# usbC_adapter.net
KiCad netlist of a schematic drawn in EAGLE
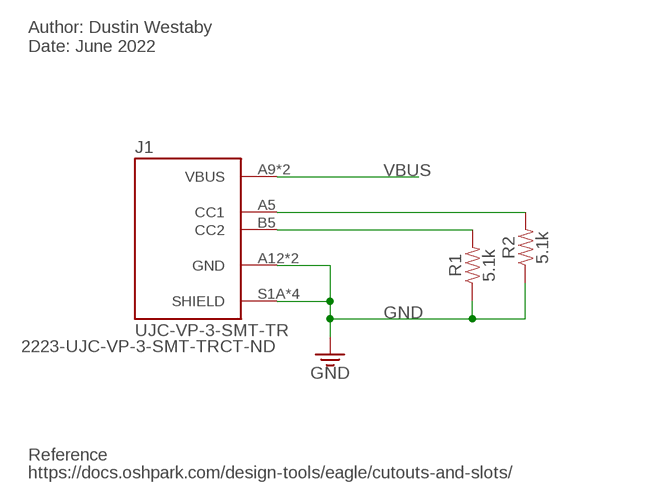
[diagram p0: schematic, sheet 1]

(export (version "E")
  (design (tool "Eeschema 10.0.6"))
  (components
    (comp (ref "J1")
      (value "UJC-VP-3-SMT-TR")
      (footprint "eagle-import:CUI_UJC-VP-3-SMT-TR")
      (fields (field (name "MANUFACTURER") "CUI Devices"))
      (libsource (lib "eagle-import") (part "UJC-VP-3-SMT-TR"))
    )
    (comp (ref "R1")
      (value "5.1k")
      (footprint "eagle-import:0402-TIGHT")
      (libsource (lib "eagle-import") (part "5.1KOHM-0402T-1/16W-1%"))
    )
    (comp (ref "R2")
      (value "5.1k")
      (footprint "eagle-import:0402-TIGHT")
      (libsource (lib "eagle-import") (part "5.1KOHM-0402T-1/16W-1%"))
    )
  )
  (nets
    (net (code "1") (name "/VBUS") (class "Default")
      (node (ref "J1") (pin "A9") (pinfunction "VBUS_A9") (pintype "power_in"))
      (node (ref "J1") (pin "B9") (pinfunction "VBUS_B9") (pintype "power_in"))
    )
    (net (code "2") (name "GND") (class "Default")
      (node (ref "J1") (pin "A12") (pinfunction "GND_A12") (pintype "power_in"))
      (node (ref "J1") (pin "B12") (pinfunction "GND_B12") (pintype "power_in"))
      (node (ref "J1") (pin "S1A") (pinfunction "SHIELD_S1A") (pintype "passive"))
      (node (ref "J1") (pin "S1B") (pinfunction "SHIELD_S1B") (pintype "passive"))
      (node (ref "J1") (pin "S2A") (pinfunction "SHIELD_S2A") (pintype "passive"))
      (node (ref "J1") (pin "S2B") (pinfunction "SHIELD_S2B") (pintype "passive"))
      (node (ref "R1") (pin "1") (pinfunction "1_1") (pintype "passive"))
      (node (ref "R2") (pin "1") (pinfunction "1_1") (pintype "passive"))
    )
    (net (code "3") (name "Net-(J1-CC1)") (class "Default")
      (node (ref "J1") (pin "A5") (pinfunction "CC1_A5") (pintype "passive"))
      (node (ref "R2") (pin "2") (pinfunction "2_2") (pintype "passive"))
    )
    (net (code "4") (name "Net-(J1-CC2)") (class "Default")
      (node (ref "J1") (pin "B5") (pinfunction "CC2_B5") (pintype "passive"))
      (node (ref "R1") (pin "2") (pinfunction "2_2") (pintype "passive"))
    )
  )
)
